# Schemat.net
KiCad netlist of a schematic drawn in EAGLE
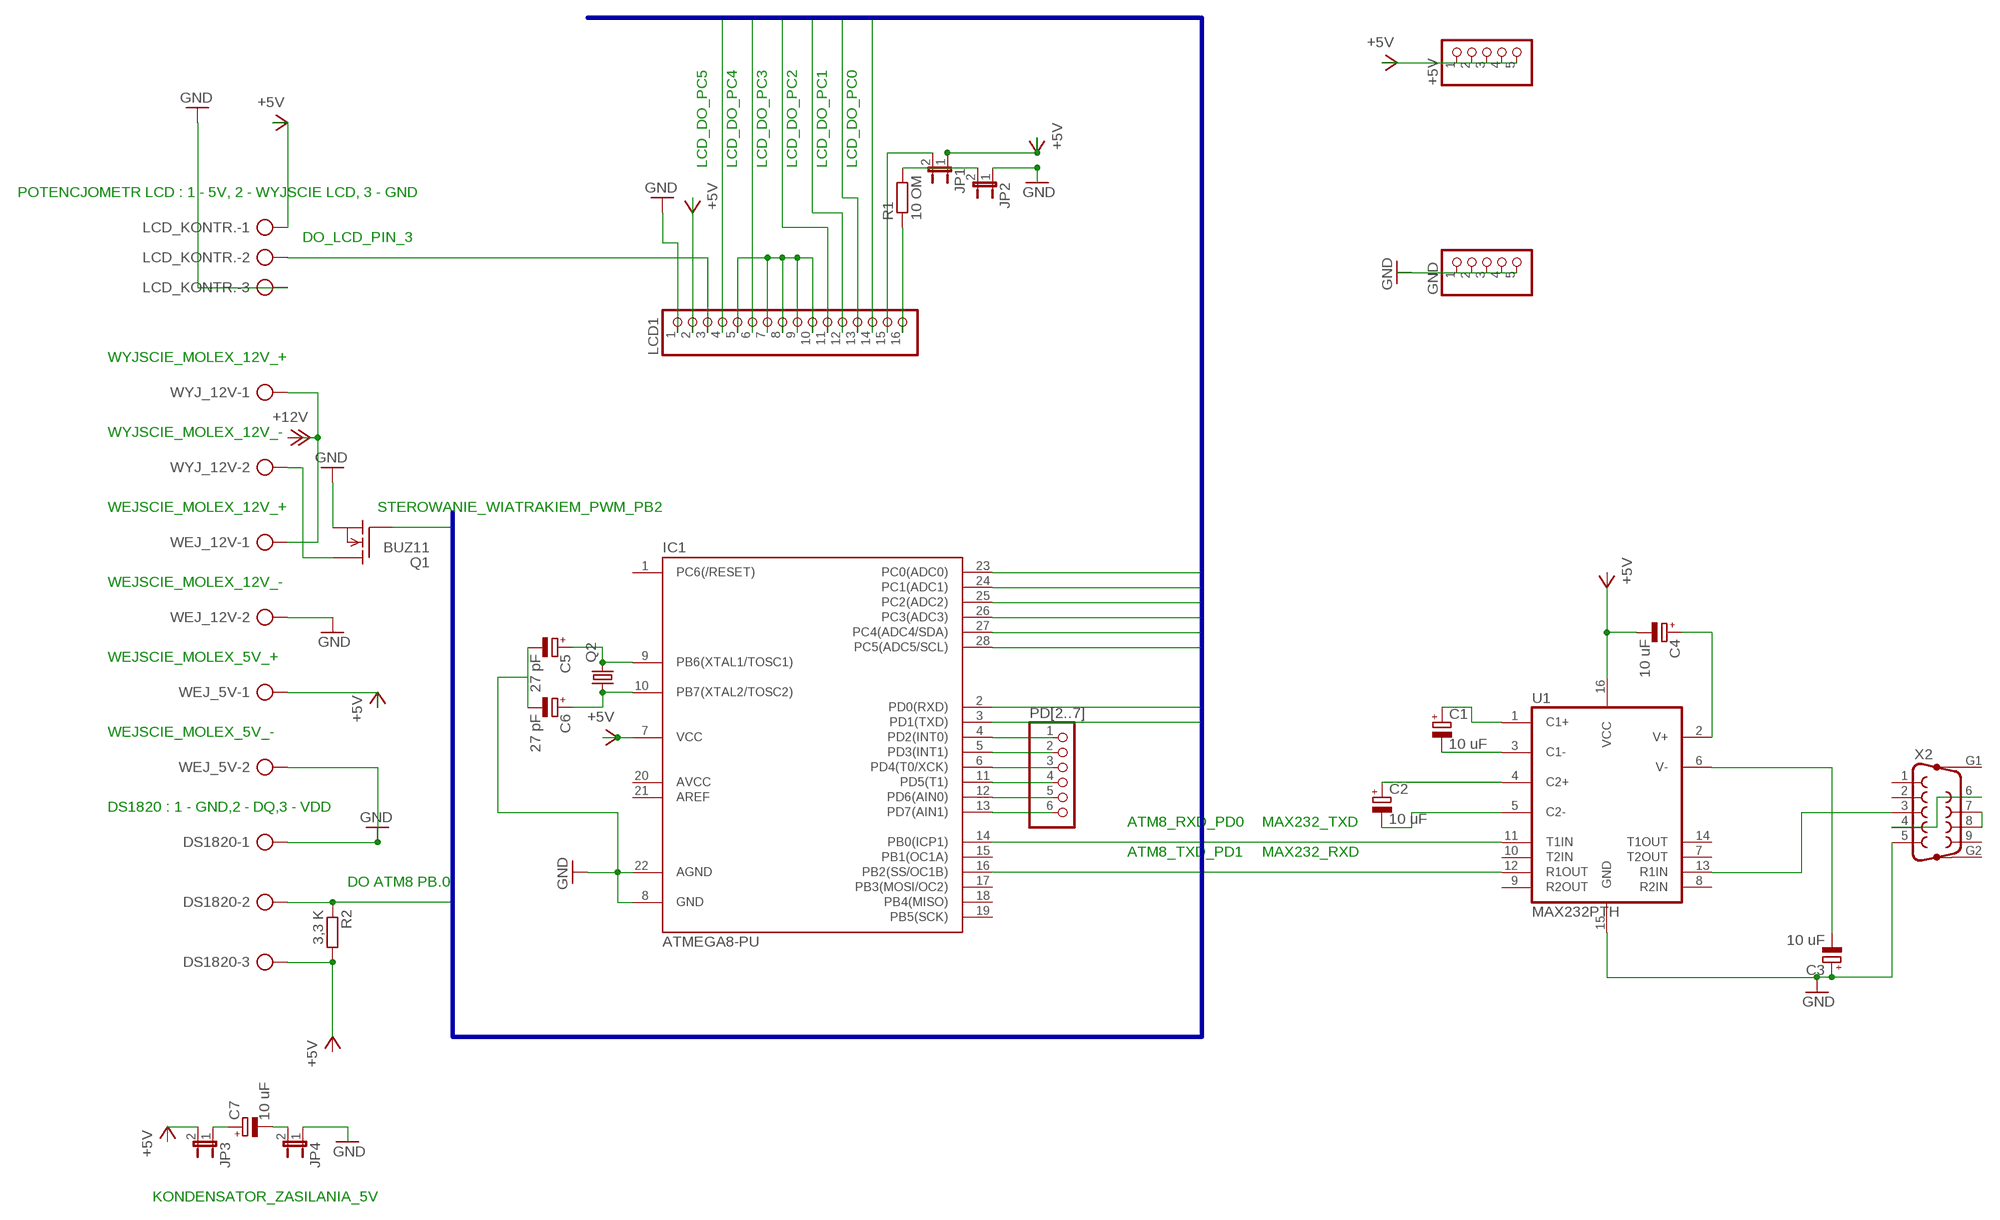
[diagram p0: schematic, sheet 1]

(export (version "E")
  (design (tool "Eeschema 10.0.6"))
  (components
    (comp (ref "+5V")
      (value "PINHD-1X5")
      (footprint "eagle-import:1X05")
      (libsource (lib "eagle-import") (part "PINHD-1X5"))
    )
    (comp (ref "C1")
      (value "10 uF")
      (footprint "eagle-import:E5-10,5")
      (libsource (lib "eagle-import") (part "CPOL-EUE5-10.5"))
    )
    (comp (ref "C2")
      (value "10 uF")
      (footprint "eagle-import:E5-10,5")
      (libsource (lib "eagle-import") (part "CPOL-EUE5-10.5"))
    )
    (comp (ref "C3")
      (value "10 uF")
      (footprint "eagle-import:E5-10,5")
      (libsource (lib "eagle-import") (part "CPOL-EUE5-10.5"))
    )
    (comp (ref "C4")
      (value "10 uF")
      (footprint "eagle-import:E5-10,5")
      (libsource (lib "eagle-import") (part "CPOL-EUE5-10.5"))
    )
    (comp (ref "C5")
      (value "27 pF")
      (footprint "eagle-import:E5-10,5")
      (libsource (lib "eagle-import") (part "CPOL-EUE5-10.5"))
    )
    (comp (ref "C6")
      (value "27 pF")
      (footprint "eagle-import:E5-10,5")
      (libsource (lib "eagle-import") (part "CPOL-EUE5-10.5"))
    )
    (comp (ref "C7")
      (value "10 uF")
      (footprint "eagle-import:E5-10,5")
      (libsource (lib "eagle-import") (part "CPOL-EUE5-10.5"))
    )
    (comp (ref "DS1820")
      (value "AK500/3-H")
      (footprint "eagle-import:AK500_3-H")
      (libsource (lib "eagle-import") (part "AK500/3-H"))
    )
    (comp (ref "GND")
      (value "PINHD-1X5")
      (footprint "eagle-import:1X05")
      (libsource (lib "eagle-import") (part "PINHD-1X5"))
    )
    (comp (ref "IC1")
      (value "ATMEGA8-PU")
      (footprint "eagle-import:DIL28-3")
      (libsource (lib "eagle-import") (part "ATMEGA8-PU"))
    )
    (comp (ref "JP1")
      (value "JP1E")
      (footprint "eagle-import:JP1")
      (libsource (lib "eagle-import") (part "JP1E"))
    )
    (comp (ref "JP2")
      (value "JP1E")
      (footprint "eagle-import:JP1")
      (libsource (lib "eagle-import") (part "JP1E"))
    )
    (comp (ref "JP3")
      (value "JP1E")
      (footprint "eagle-import:JP1")
      (libsource (lib "eagle-import") (part "JP1E"))
    )
    (comp (ref "JP4")
      (value "JP1E")
      (footprint "eagle-import:JP1")
      (libsource (lib "eagle-import") (part "JP1E"))
    )
    (comp (ref "LCD1")
      (value "PINHD-1X16")
      (footprint "eagle-import:1X16")
      (libsource (lib "eagle-import") (part "PINHD-1X16"))
    )
    (comp (ref "LCD_KONTR.")
      (value "AK500/3-H")
      (footprint "eagle-import:AK500_3-H")
      (libsource (lib "eagle-import") (part "AK500/3-H"))
    )
    (comp (ref "PD[2..7]")
      (value "PINHD-1X6")
      (footprint "eagle-import:1X06")
      (libsource (lib "eagle-import") (part "PINHD-1X6"))
    )
    (comp (ref "Q1")
      (value "BUZ11")
      (footprint "eagle-import:TO220")
      (libsource (lib "eagle-import") (part "BUZ11"))
    )
    (comp (ref "Q2")
      (value "CRYSTALHC49S")
      (footprint "eagle-import:HC49_S")
      (libsource (lib "eagle-import") (part "CRYSTALHC49S"))
    )
    (comp (ref "R1")
      (value "10 OM")
      (footprint "eagle-import:0207_15")
      (libsource (lib "eagle-import") (part "R-EU_0207/15"))
    )
    (comp (ref "R2")
      (value "3,3 K")
      (footprint "eagle-import:0207_15")
      (libsource (lib "eagle-import") (part "R-EU_0207/15"))
    )
    (comp (ref "U1")
      (value "MAX232PTH")
      (footprint "eagle-import:DIL16")
      (libsource (lib "eagle-import") (part "MAX232PTH"))
    )
    (comp (ref "WEJ_5V")
      (value "AK500/2-H")
      (footprint "eagle-import:AK500_2-H")
      (libsource (lib "eagle-import") (part "AK500/2-H"))
    )
    (comp (ref "WEJ_12V")
      (value "AK500/2-H")
      (footprint "eagle-import:AK500_2-H")
      (libsource (lib "eagle-import") (part "AK500/2-H"))
    )
    (comp (ref "WYJ_12V")
      (value "AK500/2-H")
      (footprint "eagle-import:AK500_2-H")
      (libsource (lib "eagle-import") (part "AK500/2-H"))
    )
    (comp (ref "X2")
      (value "F09HP")
      (footprint "eagle-import:F09HP")
      (libsource (lib "eagle-import") (part "F09HP"))
    )
  )
  (nets
    (net (code "1") (name "+5V") (class "Default")
      (node (ref "+5V") (pin "1") (pinfunction "1_1") (pintype "passive"))
      (node (ref "+5V") (pin "2") (pinfunction "2_2") (pintype "passive"))
      (node (ref "+5V") (pin "3") (pinfunction "3_3") (pintype "passive"))
      (node (ref "+5V") (pin "4") (pinfunction "4_4") (pintype "passive"))
      (node (ref "+5V") (pin "5") (pinfunction "5_5") (pintype "passive"))
      (node (ref "IC1") (pin "7") (pinfunction "VCC_7") (pintype "power_in"))
      (node (ref "JP1") (pin "1") (pinfunction "1_1") (pintype "passive"))
      (node (ref "JP3") (pin "2") (pinfunction "2_2") (pintype "passive"))
      (node (ref "LCD1") (pin "2") (pinfunction "2_2") (pintype "passive"))
      (node (ref "LCD_KONTR.") (pin "1") (pinfunction "KL_1") (pintype "passive"))
      (node (ref "WEJ_5V") (pin "1") (pinfunction "KL_1") (pintype "passive"))
    )
    (net (code "3") (name "/PB0") (class "Default")
      (node (ref "DS1820") (pin "2") (pinfunction "KL_2") (pintype "passive"))
      (node (ref "IC1") (pin "14") (pinfunction "PB0(ICP1)_14") (pintype "bidirectional"))
      (node (ref "R2") (pin "1") (pinfunction "1_1") (pintype "passive"))
    )
    (net (code "4") (name "/PB2") (class "Default")
      (node (ref "IC1") (pin "16") (pinfunction "PB2(SS/OC1B)_16") (pintype "bidirectional"))
      (node (ref "Q1") (pin "1") (pinfunction "G_1") (pintype "passive"))
    )
    (net (code "5") (name "/PC0") (class "Default")
      (node (ref "IC1") (pin "23") (pinfunction "PC0(ADC0)_23") (pintype "bidirectional"))
      (node (ref "LCD1") (pin "14") (pinfunction "14_14") (pintype "passive"))
    )
    (net (code "6") (name "/PC1") (class "Default")
      (node (ref "IC1") (pin "24") (pinfunction "PC1(ADC1)_24") (pintype "bidirectional"))
      (node (ref "LCD1") (pin "13") (pinfunction "13_13") (pintype "passive"))
    )
    (net (code "7") (name "/PC2") (class "Default")
      (node (ref "IC1") (pin "25") (pinfunction "PC2(ADC2)_25") (pintype "bidirectional"))
      (node (ref "LCD1") (pin "12") (pinfunction "12_12") (pintype "passive"))
    )
    (net (code "8") (name "/PC3") (class "Default")
      (node (ref "IC1") (pin "26") (pinfunction "PC3(ADC3)_26") (pintype "bidirectional"))
      (node (ref "LCD1") (pin "11") (pinfunction "11_11") (pintype "passive"))
    )
    (net (code "9") (name "/PC4") (class "Default")
      (node (ref "IC1") (pin "27") (pinfunction "PC4(ADC4/SDA)_27") (pintype "bidirectional"))
      (node (ref "LCD1") (pin "6") (pinfunction "6_6") (pintype "passive"))
    )
    (net (code "10") (name "/PC5") (class "Default")
      (node (ref "IC1") (pin "28") (pinfunction "PC5(ADC5/SCL)_28") (pintype "bidirectional"))
      (node (ref "LCD1") (pin "4") (pinfunction "4_4") (pintype "passive"))
    )
    (net (code "11") (name "/PD0") (class "Default")
      (node (ref "IC1") (pin "2") (pinfunction "PD0(RXD)_2") (pintype "bidirectional"))
      (node (ref "U1") (pin "11") (pinfunction "T1IN_11") (pintype "input"))
    )
    (net (code "12") (name "/PD1") (class "Default")
      (node (ref "IC1") (pin "3") (pinfunction "PD1(TXD)_3") (pintype "bidirectional"))
      (node (ref "U1") (pin "12") (pinfunction "R1OUT_12") (pintype "output"))
    )
    (net (code "13") (name "GND") (class "Default")
      (node (ref "C3") (pin "+") (pinfunction "+_+") (pintype "passive"))
      (node (ref "C5") (pin "-") (pinfunction "-_-") (pintype "passive"))
      (node (ref "C6") (pin "-") (pinfunction "-_-") (pintype "passive"))
      (node (ref "DS1820") (pin "1") (pinfunction "KL_1") (pintype "passive"))
      (node (ref "GND") (pin "1") (pinfunction "1_1") (pintype "passive"))
      (node (ref "GND") (pin "2") (pinfunction "2_2") (pintype "passive"))
      (node (ref "GND") (pin "3") (pinfunction "3_3") (pintype "passive"))
      (node (ref "GND") (pin "4") (pinfunction "4_4") (pintype "passive"))
      (node (ref "GND") (pin "5") (pinfunction "5_5") (pintype "passive"))
      (node (ref "IC1") (pin "22") (pinfunction "AGND_22") (pintype "power_in"))
      (node (ref "IC1") (pin "8") (pinfunction "GND_8") (pintype "power_in"))
      (node (ref "JP2") (pin "1") (pinfunction "1_1") (pintype "passive"))
      (node (ref "JP4") (pin "1") (pinfunction "1_1") (pintype "passive"))
      (node (ref "LCD1") (pin "1") (pinfunction "1_1") (pintype "passive"))
      (node (ref "LCD_KONTR.") (pin "3") (pinfunction "KL_3") (pintype "passive"))
      (node (ref "Q1") (pin "3") (pinfunction "S_3") (pintype "passive"))
      (node (ref "U1") (pin "15") (pinfunction "GND_15") (pintype "bidirectional"))
      (node (ref "WEJ_12V") (pin "2") (pinfunction "KL_2") (pintype "passive"))
      (node (ref "WEJ_5V") (pin "2") (pinfunction "KL_2") (pintype "passive"))
      (node (ref "X2") (pin "5") (pinfunction "5_5") (pintype "passive"))
    )
    (net (code "14") (name "Net-(C7-Pad+)") (class "Default")
      (node (ref "C7") (pin "+") (pinfunction "+_+") (pintype "passive"))
      (node (ref "JP3") (pin "1") (pinfunction "1_1") (pintype "passive"))
    )
    (net (code "15") (name "Net-(C7-Pad-)") (class "Default")
      (node (ref "C7") (pin "-") (pinfunction "-_-") (pintype "passive"))
      (node (ref "JP4") (pin "2") (pinfunction "2_2") (pintype "passive"))
    )
    (net (code "16") (name "Net-(DS1820C-KL)") (class "Default")
      (node (ref "DS1820") (pin "3") (pinfunction "KL_3") (pintype "passive"))
      (node (ref "R2") (pin "2") (pinfunction "2_2") (pintype "passive"))
    )
    (net (code "17") (name "Net-(IC1-PB6(XTAL1{slash}TOSC1))") (class "Default")
      (node (ref "C5") (pin "+") (pinfunction "+_+") (pintype "passive"))
      (node (ref "IC1") (pin "9") (pinfunction "PB6(XTAL1/TOSC1)_9") (pintype "bidirectional"))
      (node (ref "Q2") (pin "2") (pinfunction "2_2") (pintype "passive"))
    )
    (net (code "18") (name "Net-(IC1-PB7(XTAL2{slash}TOSC2))") (class "Default")
      (node (ref "C6") (pin "+") (pinfunction "+_+") (pintype "passive"))
      (node (ref "IC1") (pin "10") (pinfunction "PB7(XTAL2/TOSC2)_10") (pintype "bidirectional"))
      (node (ref "Q2") (pin "1") (pinfunction "1_1") (pintype "passive"))
    )
    (net (code "19") (name "Net-(IC1-PD2(INT0))") (class "Default")
      (node (ref "IC1") (pin "4") (pinfunction "PD2(INT0)_4") (pintype "bidirectional"))
      (node (ref "PD[2..7]") (pin "1") (pinfunction "1_1") (pintype "passive"))
    )
    (net (code "20") (name "Net-(IC1-PD3(INT1))") (class "Default")
      (node (ref "IC1") (pin "5") (pinfunction "PD3(INT1)_5") (pintype "bidirectional"))
      (node (ref "PD[2..7]") (pin "2") (pinfunction "2_2") (pintype "passive"))
    )
    (net (code "21") (name "Net-(IC1-PD4(T0{slash}XCK))") (class "Default")
      (node (ref "IC1") (pin "6") (pinfunction "PD4(T0/XCK)_6") (pintype "bidirectional"))
      (node (ref "PD[2..7]") (pin "3") (pinfunction "3_3") (pintype "passive"))
    )
    (net (code "22") (name "Net-(IC1-PD5(T1))") (class "Default")
      (node (ref "IC1") (pin "11") (pinfunction "PD5(T1)_11") (pintype "bidirectional"))
      (node (ref "PD[2..7]") (pin "4") (pinfunction "4_4") (pintype "passive"))
    )
    (net (code "23") (name "Net-(IC1-PD6(AIN0))") (class "Default")
      (node (ref "IC1") (pin "12") (pinfunction "PD6(AIN0)_12") (pintype "bidirectional"))
      (node (ref "PD[2..7]") (pin "5") (pinfunction "5_5") (pintype "passive"))
    )
    (net (code "24") (name "Net-(IC1-PD7(AIN1))") (class "Default")
      (node (ref "IC1") (pin "13") (pinfunction "PD7(AIN1)_13") (pintype "bidirectional"))
      (node (ref "PD[2..7]") (pin "6") (pinfunction "6_6") (pintype "passive"))
    )
    (net (code "25") (name "Net-(JP1-Pad2)") (class "Default")
      (node (ref "JP1") (pin "2") (pinfunction "2_2") (pintype "passive"))
      (node (ref "LCD1") (pin "15") (pinfunction "15_15") (pintype "passive"))
    )
    (net (code "26") (name "Net-(JP2-Pad2)") (class "Default")
      (node (ref "JP2") (pin "2") (pinfunction "2_2") (pintype "passive"))
      (node (ref "R1") (pin "2") (pinfunction "2_2") (pintype "passive"))
    )
    (net (code "27") (name "Net-(LCD1-Pad10)") (class "Default")
      (node (ref "LCD1") (pin "10") (pinfunction "10_10") (pintype "passive"))
      (node (ref "LCD1") (pin "5") (pinfunction "5_5") (pintype "passive"))
      (node (ref "LCD1") (pin "7") (pinfunction "7_7") (pintype "passive"))
      (node (ref "LCD1") (pin "8") (pinfunction "8_8") (pintype "passive"))
      (node (ref "LCD1") (pin "9") (pinfunction "9_9") (pintype "passive"))
    )
    (net (code "28") (name "Net-(LCD1-Pad16)") (class "Default")
      (node (ref "LCD1") (pin "16") (pinfunction "16_16") (pintype "passive"))
      (node (ref "R1") (pin "1") (pinfunction "1_1") (pintype "passive"))
    )
    (net (code "29") (name "Net-(LCD_KONTR.B-KL)") (class "Default")
      (node (ref "LCD1") (pin "3") (pinfunction "3_3") (pintype "passive"))
      (node (ref "LCD_KONTR.") (pin "2") (pinfunction "KL_2") (pintype "passive"))
    )
    (net (code "30") (name "Net-(Q1-D)") (class "Default")
      (node (ref "Q1") (pin "2") (pinfunction "D_2") (pintype "passive"))
      (node (ref "WYJ_12V") (pin "2") (pinfunction "KL_2") (pintype "passive"))
    )
    (net (code "31") (name "Net-(U1-C1+)") (class "Default")
      (node (ref "C1") (pin "+") (pinfunction "+_+") (pintype "passive"))
      (node (ref "U1") (pin "1") (pinfunction "C1+_1") (pintype "bidirectional"))
    )
    (net (code "32") (name "Net-(U1-C1-)") (class "Default")
      (node (ref "C1") (pin "-") (pinfunction "-_-") (pintype "passive"))
      (node (ref "U1") (pin "3") (pinfunction "C1-_3") (pintype "bidirectional"))
    )
    (net (code "33") (name "Net-(U1-C2+)") (class "Default")
      (node (ref "C2") (pin "+") (pinfunction "+_+") (pintype "passive"))
      (node (ref "U1") (pin "4") (pinfunction "C2+_4") (pintype "bidirectional"))
    )
    (net (code "34") (name "Net-(U1-C2-)") (class "Default")
      (node (ref "C2") (pin "-") (pinfunction "-_-") (pintype "passive"))
      (node (ref "U1") (pin "5") (pinfunction "C2-_5") (pintype "bidirectional"))
    )
    (net (code "35") (name "Net-(U1-R1IN)") (class "Default")
      (node (ref "U1") (pin "13") (pinfunction "R1IN_13") (pintype "input"))
      (node (ref "X2") (pin "3") (pinfunction "3_3") (pintype "passive"))
    )
    (net (code "36") (name "Net-(U1-V+)") (class "Default")
      (node (ref "C4") (pin "+") (pinfunction "+_+") (pintype "passive"))
      (node (ref "U1") (pin "2") (pinfunction "V+_2") (pintype "bidirectional"))
    )
    (net (code "37") (name "Net-(U1-V-)") (class "Default")
      (node (ref "C3") (pin "-") (pinfunction "-_-") (pintype "passive"))
      (node (ref "U1") (pin "6") (pinfunction "V-_6") (pintype "bidirectional"))
    )
    (net (code "38") (name "Net-(U1-VCC)") (class "Default")
      (node (ref "C4") (pin "-") (pinfunction "-_-") (pintype "passive"))
      (node (ref "U1") (pin "16") (pinfunction "VCC_16") (pintype "bidirectional"))
    )
    (net (code "39") (name "Net-(WEJ_12VA-KL)") (class "Default")
      (node (ref "WEJ_12V") (pin "1") (pinfunction "KL_1") (pintype "passive"))
      (node (ref "WYJ_12V") (pin "1") (pinfunction "KL_1") (pintype "passive"))
    )
    (net (code "40") (name "Net-(X2-Pad4)") (class "Default")
      (node (ref "X2") (pin "4") (pinfunction "4_4") (pintype "passive"))
      (node (ref "X2") (pin "6") (pinfunction "6_6") (pintype "passive"))
    )
    (net (code "41") (name "Net-(X2-Pad7)") (class "Default")
      (node (ref "X2") (pin "7") (pinfunction "7_7") (pintype "passive"))
      (node (ref "X2") (pin "8") (pinfunction "8_8") (pintype "passive"))
    )
    (net (code "42") (name "unconnected-(IC1-AREF-Pad21)") (class "Default")
      (node (ref "IC1") (pin "21") (pinfunction "AREF_21") (pintype "passive"))
    )
    (net (code "43") (name "unconnected-(IC1-AVCC-Pad20)") (class "Default")
      (node (ref "IC1") (pin "20") (pinfunction "AVCC_20") (pintype "passive"))
    )
    (net (code "44") (name "unconnected-(IC1-PB1(OC1A)-Pad15)") (class "Default")
      (node (ref "IC1") (pin "15") (pinfunction "PB1(OC1A)_15") (pintype "bidirectional"))
    )
    (net (code "45") (name "unconnected-(IC1-PB3(MOSI{slash}OC2)-Pad17)") (class "Default")
      (node (ref "IC1") (pin "17") (pinfunction "PB3(MOSI/OC2)_17") (pintype "bidirectional"))
    )
    (net (code "46") (name "unconnected-(IC1-PB4(MISO)-Pad18)") (class "Default")
      (node (ref "IC1") (pin "18") (pinfunction "PB4(MISO)_18") (pintype "bidirectional"))
    )
    (net (code "47") (name "unconnected-(IC1-PB5(SCK)-Pad19)") (class "Default")
      (node (ref "IC1") (pin "19") (pinfunction "PB5(SCK)_19") (pintype "bidirectional"))
    )
    (net (code "48") (name "unconnected-(IC1-PC6({slash}RESET)-Pad1)") (class "Default")
      (node (ref "IC1") (pin "1") (pinfunction "PC6(/RESET)_1") (pintype "bidirectional"))
    )
    (net (code "49") (name "unconnected-(U1-R2IN-Pad8)") (class "Default")
      (node (ref "U1") (pin "8") (pinfunction "R2IN_8") (pintype "input"))
    )
    (net (code "50") (name "unconnected-(U1-R2OUT-Pad9)") (class "Default")
      (node (ref "U1") (pin "9") (pinfunction "R2OUT_9") (pintype "output"))
    )
    (net (code "51") (name "unconnected-(U1-T1OUT-Pad14)") (class "Default")
      (node (ref "U1") (pin "14") (pinfunction "T1OUT_14") (pintype "output"))
    )
    (net (code "52") (name "unconnected-(U1-T2IN-Pad10)") (class "Default")
      (node (ref "U1") (pin "10") (pinfunction "T2IN_10") (pintype "input"))
    )
    (net (code "53") (name "unconnected-(U1-T2OUT-Pad7)") (class "Default")
      (node (ref "U1") (pin "7") (pinfunction "T2OUT_7") (pintype "output"))
    )
    (net (code "54") (name "unconnected-(X2-Pad1)") (class "Default")
      (node (ref "X2") (pin "1") (pinfunction "1_1") (pintype "passive"))
    )
    (net (code "55") (name "unconnected-(X2-Pad2)") (class "Default")
      (node (ref "X2") (pin "2") (pinfunction "2_2") (pintype "passive"))
    )
    (net (code "56") (name "unconnected-(X2-Pad9)") (class "Default")
      (node (ref "X2") (pin "9") (pinfunction "9_9") (pintype "passive"))
    )
    (net (code "57") (name "unconnected-(X2-PadG1)") (class "Default")
      (node (ref "X2") (pin "G1") (pinfunction "G1_G1") (pintype "passive"))
    )
    (net (code "58") (name "unconnected-(X2-PadG2)") (class "Default")
      (node (ref "X2") (pin "G2") (pinfunction "G2_G2") (pintype "passive"))
    )
  )
)
